# PC060HA.net
KiCad netlist of a schematic drawn in EAGLE
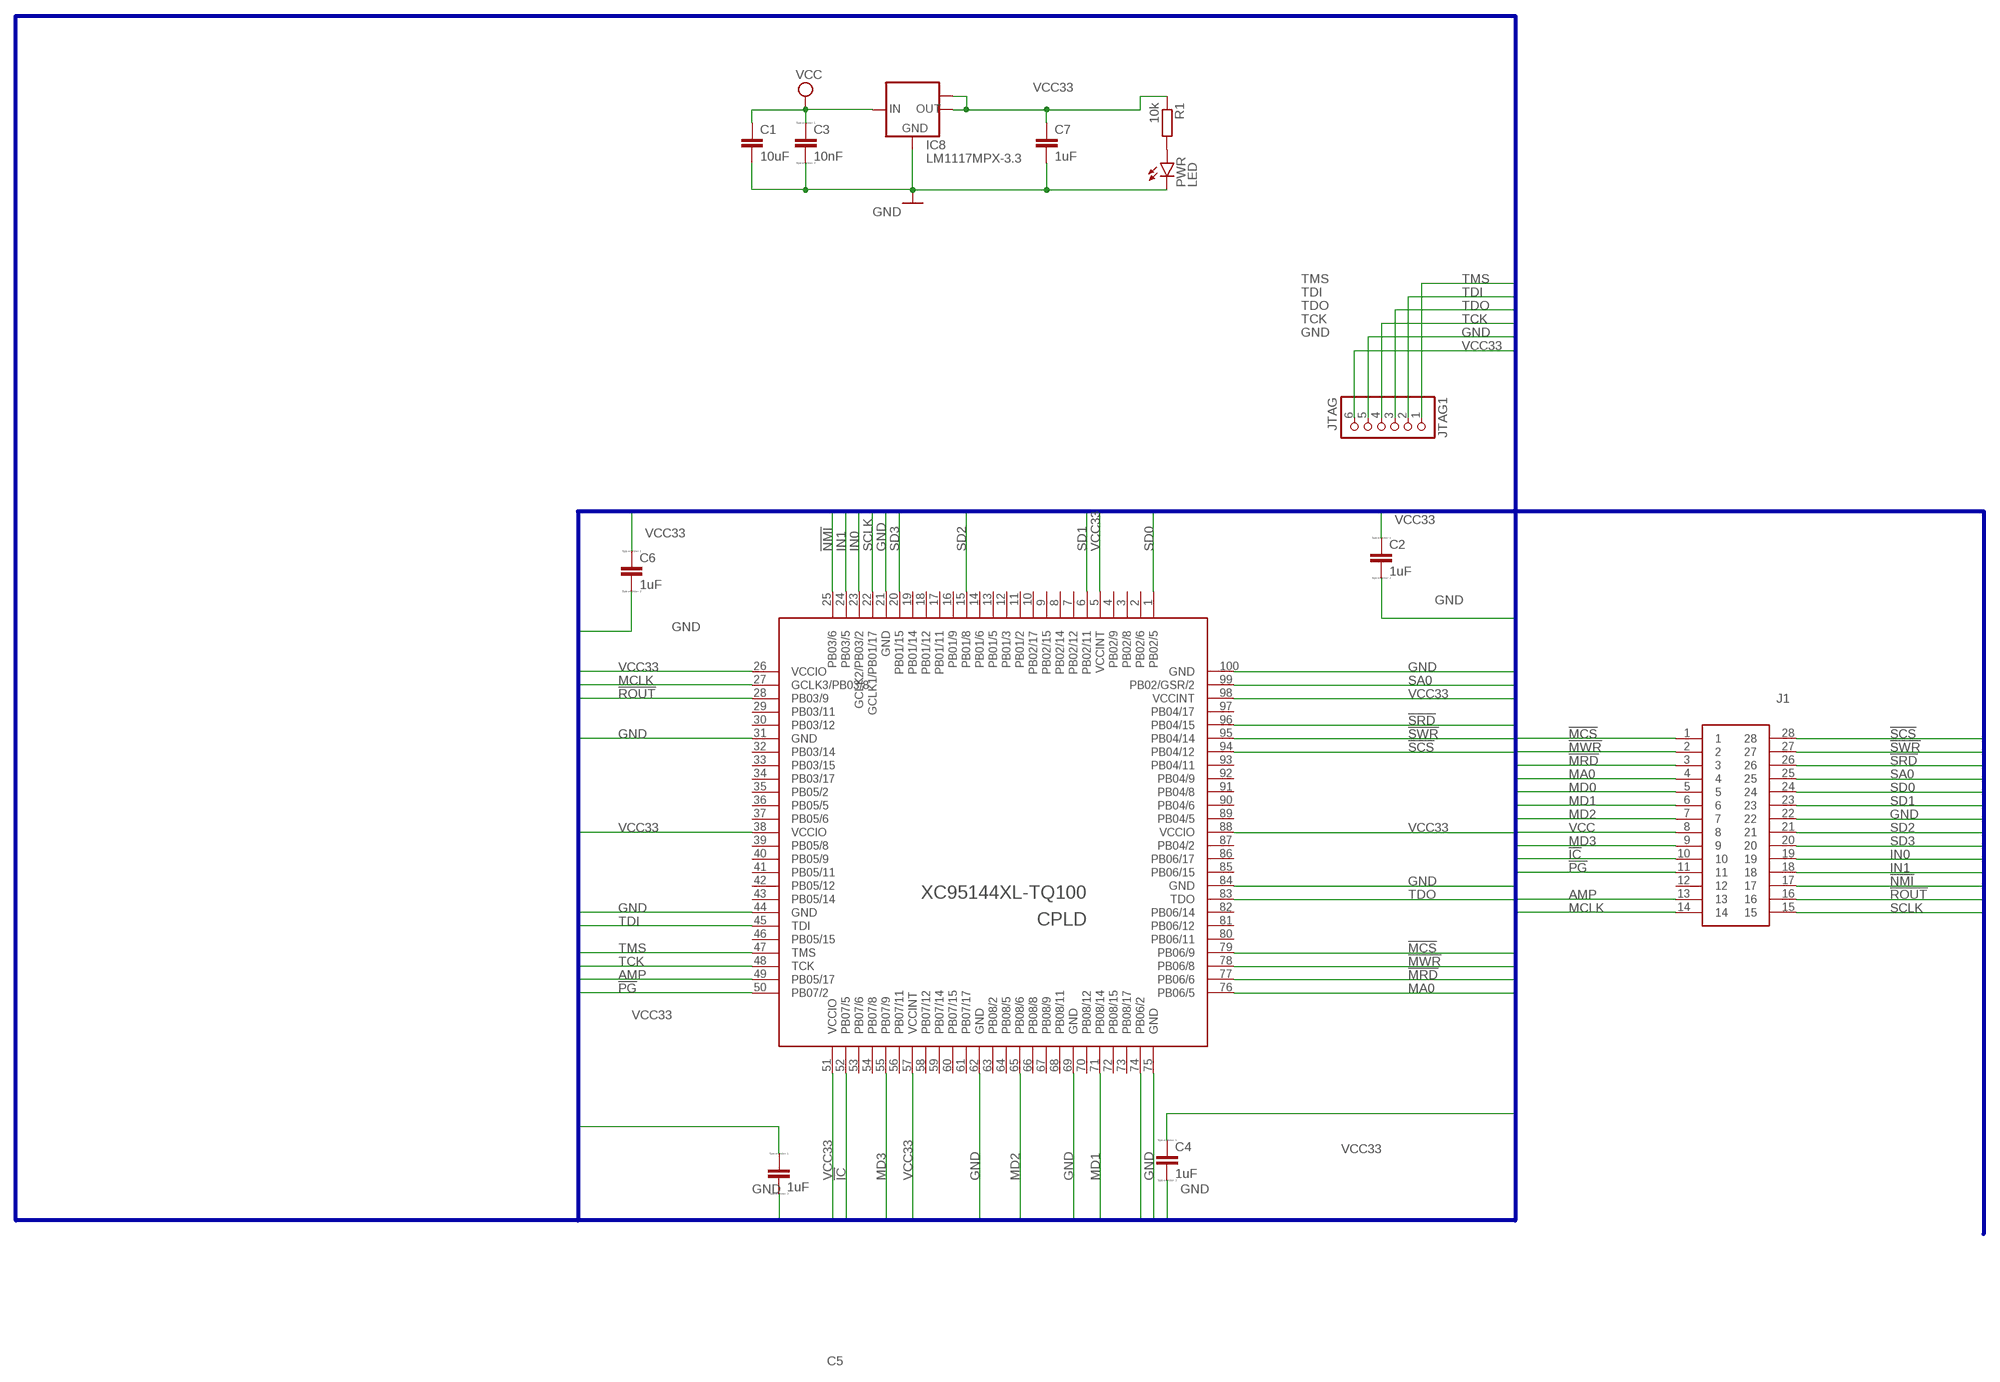
[diagram p0: schematic, sheet 1]

(export (version "E")
  (design (tool "Eeschema 10.0.6"))
  (components
    (comp (ref "C1")
      (value "10uF")
      (footprint "eagle-import:C1206")
      (libsource (lib "eagle-import") (part "C-EUC1206"))
    )
    (comp (ref "C2")
      (value "1uF")
      (footprint "eagle-import:C0603")
      (libsource (lib "eagle-import") (part "CC0603"))
    )
    (comp (ref "C3")
      (value "10nF")
      (footprint "eagle-import:C0603")
      (libsource (lib "eagle-import") (part "CC0603"))
    )
    (comp (ref "C4")
      (value "1uF")
      (footprint "eagle-import:C0603")
      (libsource (lib "eagle-import") (part "CC0603"))
    )
    (comp (ref "C5")
      (value "1uF")
      (footprint "eagle-import:C0603")
      (libsource (lib "eagle-import") (part "CC0603"))
    )
    (comp (ref "C6")
      (value "1uF")
      (footprint "eagle-import:C0603")
      (libsource (lib "eagle-import") (part "CC0603"))
    )
    (comp (ref "C7")
      (value "1uF")
      (footprint "eagle-import:C1206")
      (libsource (lib "eagle-import") (part "C-EUC1206"))
    )
    (comp (ref "CPLD")
      (value "XC95144XL-TQ100")
      (footprint "eagle-import:TQFP100")
      (libsource (lib "eagle-import") (part "XC95144XL-TQ100"))
    )
    (comp (ref "IC8")
      (value "LM1117MPX-3.3")
      (footprint "eagle-import:SOT223")
      (libsource (lib "eagle-import") (part "LM1117MPX-3.3"))
    )
    (comp (ref "J1")
      (value "150-10-628-00-106161")
      (footprint "eagle-import:1501062800106161")
      (libsource (lib "eagle-import") (part "150-10-628-00-106161"))
    )
    (comp (ref "JTAG1")
      (value "JTAG")
      (footprint "eagle-import:1X06_ROUND")
      (libsource (lib "eagle-import") (part "HEADER-1X6ROUND"))
    )
    (comp (ref "PWR")
      (value "LED")
      (footprint "eagle-import:SML0805")
      (libsource (lib "eagle-import") (part "LEDSML0805"))
    )
    (comp (ref "R1")
      (value "10k")
      (footprint "eagle-import:R0603")
      (libsource (lib "eagle-import") (part "R-EU_R0603"))
    )
  )
  (nets
    (net (code "1") (name "/AMP") (class "Default")
      (node (ref "CPLD") (pin "49") (pinfunction "PB05/17_49") (pintype "bidirectional"))
      (node (ref "J1") (pin "13") (pinfunction "13_13") (pintype "bidirectional"))
    )
    (net (code "2") (name "/IN0") (class "Default")
      (node (ref "CPLD") (pin "23") (pinfunction "GCLK2/PB03/2_23") (pintype "bidirectional"))
      (node (ref "J1") (pin "19") (pinfunction "19_19") (pintype "bidirectional"))
    )
    (net (code "3") (name "/IN1") (class "Default")
      (node (ref "CPLD") (pin "24") (pinfunction "PB03/5_24") (pintype "bidirectional"))
      (node (ref "J1") (pin "18") (pinfunction "18_18") (pintype "bidirectional"))
    )
    (net (code "4") (name "/MA0") (class "Default")
      (node (ref "CPLD") (pin "76") (pinfunction "PB06/5_76") (pintype "bidirectional"))
      (node (ref "J1") (pin "4") (pinfunction "4_4") (pintype "bidirectional"))
    )
    (net (code "5") (name "/MCLK") (class "Default")
      (node (ref "CPLD") (pin "27") (pinfunction "GCLK3/PB03/8_27") (pintype "bidirectional"))
      (node (ref "J1") (pin "14") (pinfunction "14_14") (pintype "bidirectional"))
    )
    (net (code "6") (name "/MD0") (class "Default")
      (node (ref "CPLD") (pin "74") (pinfunction "PB06/2_74") (pintype "bidirectional"))
      (node (ref "J1") (pin "5") (pinfunction "5_5") (pintype "bidirectional"))
    )
    (net (code "7") (name "/MD1") (class "Default")
      (node (ref "CPLD") (pin "71") (pinfunction "PB08/14_71") (pintype "bidirectional"))
      (node (ref "J1") (pin "6") (pinfunction "6_6") (pintype "bidirectional"))
    )
    (net (code "8") (name "/MD2") (class "Default")
      (node (ref "CPLD") (pin "65") (pinfunction "PB08/6_65") (pintype "bidirectional"))
      (node (ref "J1") (pin "7") (pinfunction "7_7") (pintype "bidirectional"))
    )
    (net (code "9") (name "/MD3") (class "Default")
      (node (ref "CPLD") (pin "55") (pinfunction "PB07/9_55") (pintype "bidirectional"))
      (node (ref "J1") (pin "9") (pinfunction "9_9") (pintype "bidirectional"))
    )
    (net (code "10") (name "/SA0") (class "Default")
      (node (ref "CPLD") (pin "99") (pinfunction "PB02/GSR/2_99") (pintype "bidirectional"))
      (node (ref "J1") (pin "25") (pinfunction "25_25") (pintype "bidirectional"))
    )
    (net (code "11") (name "/SCLK") (class "Default")
      (node (ref "CPLD") (pin "22") (pinfunction "GCLK1/PB01/17_22") (pintype "bidirectional"))
      (node (ref "J1") (pin "15") (pinfunction "15_15") (pintype "bidirectional"))
    )
    (net (code "12") (name "/SD0") (class "Default")
      (node (ref "CPLD") (pin "1") (pinfunction "PB02/5_1") (pintype "bidirectional"))
      (node (ref "J1") (pin "24") (pinfunction "24_24") (pintype "bidirectional"))
    )
    (net (code "13") (name "/SD1") (class "Default")
      (node (ref "CPLD") (pin "6") (pinfunction "PB02/11_6") (pintype "bidirectional"))
      (node (ref "J1") (pin "23") (pinfunction "23_23") (pintype "bidirectional"))
    )
    (net (code "14") (name "/SD2") (class "Default")
      (node (ref "CPLD") (pin "15") (pinfunction "PB01/8_15") (pintype "bidirectional"))
      (node (ref "J1") (pin "21") (pinfunction "21_21") (pintype "bidirectional"))
    )
    (net (code "15") (name "/SD3") (class "Default")
      (node (ref "CPLD") (pin "20") (pinfunction "PB01/15_20") (pintype "bidirectional"))
      (node (ref "J1") (pin "20") (pinfunction "20_20") (pintype "bidirectional"))
    )
    (net (code "16") (name "/TCK") (class "Default")
      (node (ref "CPLD") (pin "48") (pinfunction "TCK_48") (pintype "bidirectional"))
      (node (ref "JTAG1") (pin "4") (pinfunction "4_4") (pintype "passive"))
    )
    (net (code "17") (name "/TDI") (class "Default")
      (node (ref "CPLD") (pin "45") (pinfunction "TDI_45") (pintype "bidirectional"))
      (node (ref "JTAG1") (pin "2") (pinfunction "2_2") (pintype "passive"))
    )
    (net (code "18") (name "/TDO") (class "Default")
      (node (ref "CPLD") (pin "83") (pinfunction "TDO_83") (pintype "bidirectional"))
      (node (ref "JTAG1") (pin "3") (pinfunction "3_3") (pintype "passive"))
    )
    (net (code "19") (name "/TMS") (class "Default")
      (node (ref "CPLD") (pin "47") (pinfunction "TMS_47") (pintype "bidirectional"))
      (node (ref "JTAG1") (pin "1") (pinfunction "1_1") (pintype "passive"))
    )
    (net (code "20") (name "/VCC33") (class "Default")
      (node (ref "C2") (pin "1") (pinfunction "1_1") (pintype "passive"))
      (node (ref "C4") (pin "1") (pinfunction "1_1") (pintype "passive"))
      (node (ref "C5") (pin "1") (pinfunction "1_1") (pintype "passive"))
      (node (ref "C6") (pin "1") (pinfunction "1_1") (pintype "passive"))
      (node (ref "C7") (pin "1") (pinfunction "1_1") (pintype "passive"))
      (node (ref "CPLD") (pin "26") (pinfunction "VCCIO_26") (pintype "bidirectional"))
      (node (ref "CPLD") (pin "38") (pinfunction "VCCIO_38") (pintype "bidirectional"))
      (node (ref "CPLD") (pin "5") (pinfunction "VCCINT_5") (pintype "bidirectional"))
      (node (ref "CPLD") (pin "51") (pinfunction "VCCIO_51") (pintype "bidirectional"))
      (node (ref "CPLD") (pin "57") (pinfunction "VCCINT_57") (pintype "bidirectional"))
      (node (ref "CPLD") (pin "88") (pinfunction "VCCIO_88") (pintype "bidirectional"))
      (node (ref "CPLD") (pin "98") (pinfunction "VCCINT_98") (pintype "bidirectional"))
      (node (ref "IC8") (pin "2") (pinfunction "OUT_2") (pintype "passive"))
      (node (ref "IC8") (pin "TAB") (pinfunction "OUT1_TAB") (pintype "passive"))
      (node (ref "JTAG1") (pin "6") (pinfunction "6_6") (pintype "passive"))
      (node (ref "R1") (pin "1") (pinfunction "1_1") (pintype "passive"))
    )
    (net (code "21") (name "/~{IC}") (class "Default")
      (node (ref "CPLD") (pin "52") (pinfunction "PB07/5_52") (pintype "bidirectional"))
      (node (ref "J1") (pin "10") (pinfunction "10_10") (pintype "bidirectional"))
    )
    (net (code "22") (name "/~{MCS}") (class "Default")
      (node (ref "CPLD") (pin "79") (pinfunction "PB06/9_79") (pintype "bidirectional"))
      (node (ref "J1") (pin "1") (pinfunction "1_1") (pintype "bidirectional"))
    )
    (net (code "23") (name "/~{MRD}") (class "Default")
      (node (ref "CPLD") (pin "77") (pinfunction "PB06/6_77") (pintype "bidirectional"))
      (node (ref "J1") (pin "3") (pinfunction "3_3") (pintype "bidirectional"))
    )
    (net (code "24") (name "/~{MWR}") (class "Default")
      (node (ref "CPLD") (pin "78") (pinfunction "PB06/8_78") (pintype "bidirectional"))
      (node (ref "J1") (pin "2") (pinfunction "2_2") (pintype "bidirectional"))
    )
    (net (code "25") (name "/~{NMI}") (class "Default")
      (node (ref "CPLD") (pin "25") (pinfunction "PB03/6_25") (pintype "bidirectional"))
      (node (ref "J1") (pin "17") (pinfunction "17_17") (pintype "bidirectional"))
    )
    (net (code "26") (name "/~{PG}") (class "Default")
      (node (ref "CPLD") (pin "50") (pinfunction "PB07/2_50") (pintype "bidirectional"))
      (node (ref "J1") (pin "11") (pinfunction "11_11") (pintype "bidirectional"))
    )
    (net (code "27") (name "/~{ROUT}") (class "Default")
      (node (ref "CPLD") (pin "28") (pinfunction "PB03/9_28") (pintype "bidirectional"))
      (node (ref "J1") (pin "16") (pinfunction "16_16") (pintype "bidirectional"))
    )
    (net (code "28") (name "/~{SCS}") (class "Default")
      (node (ref "CPLD") (pin "94") (pinfunction "PB04/12_94") (pintype "bidirectional"))
      (node (ref "J1") (pin "28") (pinfunction "28_28") (pintype "bidirectional"))
    )
    (net (code "29") (name "/~{SRD}") (class "Default")
      (node (ref "CPLD") (pin "96") (pinfunction "PB04/15_96") (pintype "bidirectional"))
      (node (ref "J1") (pin "26") (pinfunction "26_26") (pintype "bidirectional"))
    )
    (net (code "30") (name "/~{SWR}") (class "Default")
      (node (ref "CPLD") (pin "95") (pinfunction "PB04/14_95") (pintype "bidirectional"))
      (node (ref "J1") (pin "27") (pinfunction "27_27") (pintype "bidirectional"))
    )
    (net (code "31") (name "GND") (class "Default")
      (node (ref "C1") (pin "2") (pinfunction "2_2") (pintype "passive"))
      (node (ref "C2") (pin "2") (pinfunction "2_2") (pintype "passive"))
      (node (ref "C3") (pin "2") (pinfunction "2_2") (pintype "passive"))
      (node (ref "C4") (pin "2") (pinfunction "2_2") (pintype "passive"))
      (node (ref "C5") (pin "2") (pinfunction "2_2") (pintype "passive"))
      (node (ref "C6") (pin "2") (pinfunction "2_2") (pintype "passive"))
      (node (ref "C7") (pin "2") (pinfunction "2_2") (pintype "passive"))
      (node (ref "CPLD") (pin "100") (pinfunction "GND_100") (pintype "bidirectional"))
      (node (ref "CPLD") (pin "21") (pinfunction "GND_21") (pintype "bidirectional"))
      (node (ref "CPLD") (pin "31") (pinfunction "GND_31") (pintype "bidirectional"))
      (node (ref "CPLD") (pin "44") (pinfunction "GND_44") (pintype "bidirectional"))
      (node (ref "CPLD") (pin "62") (pinfunction "GND_62") (pintype "bidirectional"))
      (node (ref "CPLD") (pin "69") (pinfunction "GND_69") (pintype "bidirectional"))
      (node (ref "CPLD") (pin "75") (pinfunction "GND_75") (pintype "bidirectional"))
      (node (ref "CPLD") (pin "84") (pinfunction "GND_84") (pintype "bidirectional"))
      (node (ref "IC8") (pin "1") (pinfunction "GND_1") (pintype "input"))
      (node (ref "J1") (pin "22") (pinfunction "22_22") (pintype "bidirectional"))
      (node (ref "JTAG1") (pin "5") (pinfunction "5_5") (pintype "passive"))
      (node (ref "PWR") (pin "C") (pinfunction "C_C") (pintype "passive"))
    )
    (net (code "32") (name "Net-(PWR-PadA)") (class "Default")
      (node (ref "PWR") (pin "A") (pinfunction "A_A") (pintype "passive"))
      (node (ref "R1") (pin "2") (pinfunction "2_2") (pintype "passive"))
    )
    (net (code "33") (name "VCC") (class "Default")
      (node (ref "C1") (pin "1") (pinfunction "1_1") (pintype "passive"))
      (node (ref "C3") (pin "1") (pinfunction "1_1") (pintype "passive"))
      (node (ref "IC8") (pin "3") (pinfunction "IN_3") (pintype "input"))
      (node (ref "J1") (pin "8") (pinfunction "8_8") (pintype "bidirectional"))
    )
    (net (code "34") (name "unconnected-(CPLD-PB01{slash}2-Pad11)") (class "Default")
      (node (ref "CPLD") (pin "11") (pinfunction "PB01/2_11") (pintype "bidirectional"))
    )
    (net (code "35") (name "unconnected-(CPLD-PB01{slash}3-Pad12)") (class "Default")
      (node (ref "CPLD") (pin "12") (pinfunction "PB01/3_12") (pintype "bidirectional"))
    )
    (net (code "36") (name "unconnected-(CPLD-PB01{slash}5-Pad13)") (class "Default")
      (node (ref "CPLD") (pin "13") (pinfunction "PB01/5_13") (pintype "bidirectional"))
    )
    (net (code "37") (name "unconnected-(CPLD-PB01{slash}6-Pad14)") (class "Default")
      (node (ref "CPLD") (pin "14") (pinfunction "PB01/6_14") (pintype "bidirectional"))
    )
    (net (code "38") (name "unconnected-(CPLD-PB01{slash}9-Pad16)") (class "Default")
      (node (ref "CPLD") (pin "16") (pinfunction "PB01/9_16") (pintype "bidirectional"))
    )
    (net (code "39") (name "unconnected-(CPLD-PB01{slash}11-Pad17)") (class "Default")
      (node (ref "CPLD") (pin "17") (pinfunction "PB01/11_17") (pintype "bidirectional"))
    )
    (net (code "40") (name "unconnected-(CPLD-PB01{slash}12-Pad18)") (class "Default")
      (node (ref "CPLD") (pin "18") (pinfunction "PB01/12_18") (pintype "bidirectional"))
    )
    (net (code "41") (name "unconnected-(CPLD-PB01{slash}14-Pad19)") (class "Default")
      (node (ref "CPLD") (pin "19") (pinfunction "PB01/14_19") (pintype "bidirectional"))
    )
    (net (code "42") (name "unconnected-(CPLD-PB02{slash}6-Pad2)") (class "Default")
      (node (ref "CPLD") (pin "2") (pinfunction "PB02/6_2") (pintype "bidirectional"))
    )
    (net (code "43") (name "unconnected-(CPLD-PB02{slash}8-Pad3)") (class "Default")
      (node (ref "CPLD") (pin "3") (pinfunction "PB02/8_3") (pintype "bidirectional"))
    )
    (net (code "44") (name "unconnected-(CPLD-PB02{slash}9-Pad4)") (class "Default")
      (node (ref "CPLD") (pin "4") (pinfunction "PB02/9_4") (pintype "bidirectional"))
    )
    (net (code "45") (name "unconnected-(CPLD-PB02{slash}12-Pad7)") (class "Default")
      (node (ref "CPLD") (pin "7") (pinfunction "PB02/12_7") (pintype "bidirectional"))
    )
    (net (code "46") (name "unconnected-(CPLD-PB02{slash}14-Pad8)") (class "Default")
      (node (ref "CPLD") (pin "8") (pinfunction "PB02/14_8") (pintype "bidirectional"))
    )
    (net (code "47") (name "unconnected-(CPLD-PB02{slash}15-Pad9)") (class "Default")
      (node (ref "CPLD") (pin "9") (pinfunction "PB02/15_9") (pintype "bidirectional"))
    )
    (net (code "48") (name "unconnected-(CPLD-PB02{slash}17-Pad10)") (class "Default")
      (node (ref "CPLD") (pin "10") (pinfunction "PB02/17_10") (pintype "bidirectional"))
    )
    (net (code "49") (name "unconnected-(CPLD-PB03{slash}11-Pad29)") (class "Default")
      (node (ref "CPLD") (pin "29") (pinfunction "PB03/11_29") (pintype "bidirectional"))
    )
    (net (code "50") (name "unconnected-(CPLD-PB03{slash}12-Pad30)") (class "Default")
      (node (ref "CPLD") (pin "30") (pinfunction "PB03/12_30") (pintype "bidirectional"))
    )
    (net (code "51") (name "unconnected-(CPLD-PB03{slash}14-Pad32)") (class "Default")
      (node (ref "CPLD") (pin "32") (pinfunction "PB03/14_32") (pintype "bidirectional"))
    )
    (net (code "52") (name "unconnected-(CPLD-PB03{slash}15-Pad33)") (class "Default")
      (node (ref "CPLD") (pin "33") (pinfunction "PB03/15_33") (pintype "bidirectional"))
    )
    (net (code "53") (name "unconnected-(CPLD-PB03{slash}17-Pad34)") (class "Default")
      (node (ref "CPLD") (pin "34") (pinfunction "PB03/17_34") (pintype "bidirectional"))
    )
    (net (code "54") (name "unconnected-(CPLD-PB04{slash}2-Pad87)") (class "Default")
      (node (ref "CPLD") (pin "87") (pinfunction "PB04/2_87") (pintype "bidirectional"))
    )
    (net (code "55") (name "unconnected-(CPLD-PB04{slash}5-Pad89)") (class "Default")
      (node (ref "CPLD") (pin "89") (pinfunction "PB04/5_89") (pintype "bidirectional"))
    )
    (net (code "56") (name "unconnected-(CPLD-PB04{slash}6-Pad90)") (class "Default")
      (node (ref "CPLD") (pin "90") (pinfunction "PB04/6_90") (pintype "bidirectional"))
    )
    (net (code "57") (name "unconnected-(CPLD-PB04{slash}8-Pad91)") (class "Default")
      (node (ref "CPLD") (pin "91") (pinfunction "PB04/8_91") (pintype "bidirectional"))
    )
    (net (code "58") (name "unconnected-(CPLD-PB04{slash}9-Pad92)") (class "Default")
      (node (ref "CPLD") (pin "92") (pinfunction "PB04/9_92") (pintype "bidirectional"))
    )
    (net (code "59") (name "unconnected-(CPLD-PB04{slash}11-Pad93)") (class "Default")
      (node (ref "CPLD") (pin "93") (pinfunction "PB04/11_93") (pintype "bidirectional"))
    )
    (net (code "60") (name "unconnected-(CPLD-PB04{slash}17-Pad97)") (class "Default")
      (node (ref "CPLD") (pin "97") (pinfunction "PB04/17_97") (pintype "bidirectional"))
    )
    (net (code "61") (name "unconnected-(CPLD-PB05{slash}2-Pad35)") (class "Default")
      (node (ref "CPLD") (pin "35") (pinfunction "PB05/2_35") (pintype "bidirectional"))
    )
    (net (code "62") (name "unconnected-(CPLD-PB05{slash}5-Pad36)") (class "Default")
      (node (ref "CPLD") (pin "36") (pinfunction "PB05/5_36") (pintype "bidirectional"))
    )
    (net (code "63") (name "unconnected-(CPLD-PB05{slash}6-Pad37)") (class "Default")
      (node (ref "CPLD") (pin "37") (pinfunction "PB05/6_37") (pintype "bidirectional"))
    )
    (net (code "64") (name "unconnected-(CPLD-PB05{slash}8-Pad39)") (class "Default")
      (node (ref "CPLD") (pin "39") (pinfunction "PB05/8_39") (pintype "bidirectional"))
    )
    (net (code "65") (name "unconnected-(CPLD-PB05{slash}9-Pad40)") (class "Default")
      (node (ref "CPLD") (pin "40") (pinfunction "PB05/9_40") (pintype "bidirectional"))
    )
    (net (code "66") (name "unconnected-(CPLD-PB05{slash}11-Pad41)") (class "Default")
      (node (ref "CPLD") (pin "41") (pinfunction "PB05/11_41") (pintype "bidirectional"))
    )
    (net (code "67") (name "unconnected-(CPLD-PB05{slash}12-Pad42)") (class "Default")
      (node (ref "CPLD") (pin "42") (pinfunction "PB05/12_42") (pintype "bidirectional"))
    )
    (net (code "68") (name "unconnected-(CPLD-PB05{slash}14-Pad43)") (class "Default")
      (node (ref "CPLD") (pin "43") (pinfunction "PB05/14_43") (pintype "bidirectional"))
    )
    (net (code "69") (name "unconnected-(CPLD-PB05{slash}15-Pad46)") (class "Default")
      (node (ref "CPLD") (pin "46") (pinfunction "PB05/15_46") (pintype "bidirectional"))
    )
    (net (code "70") (name "unconnected-(CPLD-PB06{slash}11-Pad80)") (class "Default")
      (node (ref "CPLD") (pin "80") (pinfunction "PB06/11_80") (pintype "bidirectional"))
    )
    (net (code "71") (name "unconnected-(CPLD-PB06{slash}12-Pad81)") (class "Default")
      (node (ref "CPLD") (pin "81") (pinfunction "PB06/12_81") (pintype "bidirectional"))
    )
    (net (code "72") (name "unconnected-(CPLD-PB06{slash}14-Pad82)") (class "Default")
      (node (ref "CPLD") (pin "82") (pinfunction "PB06/14_82") (pintype "bidirectional"))
    )
    (net (code "73") (name "unconnected-(CPLD-PB06{slash}15-Pad85)") (class "Default")
      (node (ref "CPLD") (pin "85") (pinfunction "PB06/15_85") (pintype "bidirectional"))
    )
    (net (code "74") (name "unconnected-(CPLD-PB06{slash}17-Pad86)") (class "Default")
      (node (ref "CPLD") (pin "86") (pinfunction "PB06/17_86") (pintype "bidirectional"))
    )
    (net (code "75") (name "unconnected-(CPLD-PB07{slash}6-Pad53)") (class "Default")
      (node (ref "CPLD") (pin "53") (pinfunction "PB07/6_53") (pintype "bidirectional"))
    )
    (net (code "76") (name "unconnected-(CPLD-PB07{slash}8-Pad54)") (class "Default")
      (node (ref "CPLD") (pin "54") (pinfunction "PB07/8_54") (pintype "bidirectional"))
    )
    (net (code "77") (name "unconnected-(CPLD-PB07{slash}11-Pad56)") (class "Default")
      (node (ref "CPLD") (pin "56") (pinfunction "PB07/11_56") (pintype "bidirectional"))
    )
    (net (code "78") (name "unconnected-(CPLD-PB07{slash}12-Pad58)") (class "Default")
      (node (ref "CPLD") (pin "58") (pinfunction "PB07/12_58") (pintype "bidirectional"))
    )
    (net (code "79") (name "unconnected-(CPLD-PB07{slash}14-Pad59)") (class "Default")
      (node (ref "CPLD") (pin "59") (pinfunction "PB07/14_59") (pintype "bidirectional"))
    )
    (net (code "80") (name "unconnected-(CPLD-PB07{slash}15-Pad60)") (class "Default")
      (node (ref "CPLD") (pin "60") (pinfunction "PB07/15_60") (pintype "bidirectional"))
    )
    (net (code "81") (name "unconnected-(CPLD-PB07{slash}17-Pad61)") (class "Default")
      (node (ref "CPLD") (pin "61") (pinfunction "PB07/17_61") (pintype "bidirectional"))
    )
    (net (code "82") (name "unconnected-(CPLD-PB08{slash}2-Pad63)") (class "Default")
      (node (ref "CPLD") (pin "63") (pinfunction "PB08/2_63") (pintype "bidirectional"))
    )
    (net (code "83") (name "unconnected-(CPLD-PB08{slash}5-Pad64)") (class "Default")
      (node (ref "CPLD") (pin "64") (pinfunction "PB08/5_64") (pintype "bidirectional"))
    )
    (net (code "84") (name "unconnected-(CPLD-PB08{slash}8-Pad66)") (class "Default")
      (node (ref "CPLD") (pin "66") (pinfunction "PB08/8_66") (pintype "bidirectional"))
    )
    (net (code "85") (name "unconnected-(CPLD-PB08{slash}9-Pad67)") (class "Default")
      (node (ref "CPLD") (pin "67") (pinfunction "PB08/9_67") (pintype "bidirectional"))
    )
    (net (code "86") (name "unconnected-(CPLD-PB08{slash}11-Pad68)") (class "Default")
      (node (ref "CPLD") (pin "68") (pinfunction "PB08/11_68") (pintype "bidirectional"))
    )
    (net (code "87") (name "unconnected-(CPLD-PB08{slash}12-Pad70)") (class "Default")
      (node (ref "CPLD") (pin "70") (pinfunction "PB08/12_70") (pintype "bidirectional"))
    )
    (net (code "88") (name "unconnected-(CPLD-PB08{slash}15-Pad72)") (class "Default")
      (node (ref "CPLD") (pin "72") (pinfunction "PB08/15_72") (pintype "bidirectional"))
    )
    (net (code "89") (name "unconnected-(CPLD-PB08{slash}17-Pad73)") (class "Default")
      (node (ref "CPLD") (pin "73") (pinfunction "PB08/17_73") (pintype "bidirectional"))
    )
    (net (code "90") (name "unconnected-(J1-Pad12)") (class "Default")
      (node (ref "J1") (pin "12") (pinfunction "12_12") (pintype "bidirectional"))
    )
  )
)
